# bbhTiny84.net
KiCad netlist of a schematic drawn in EAGLE
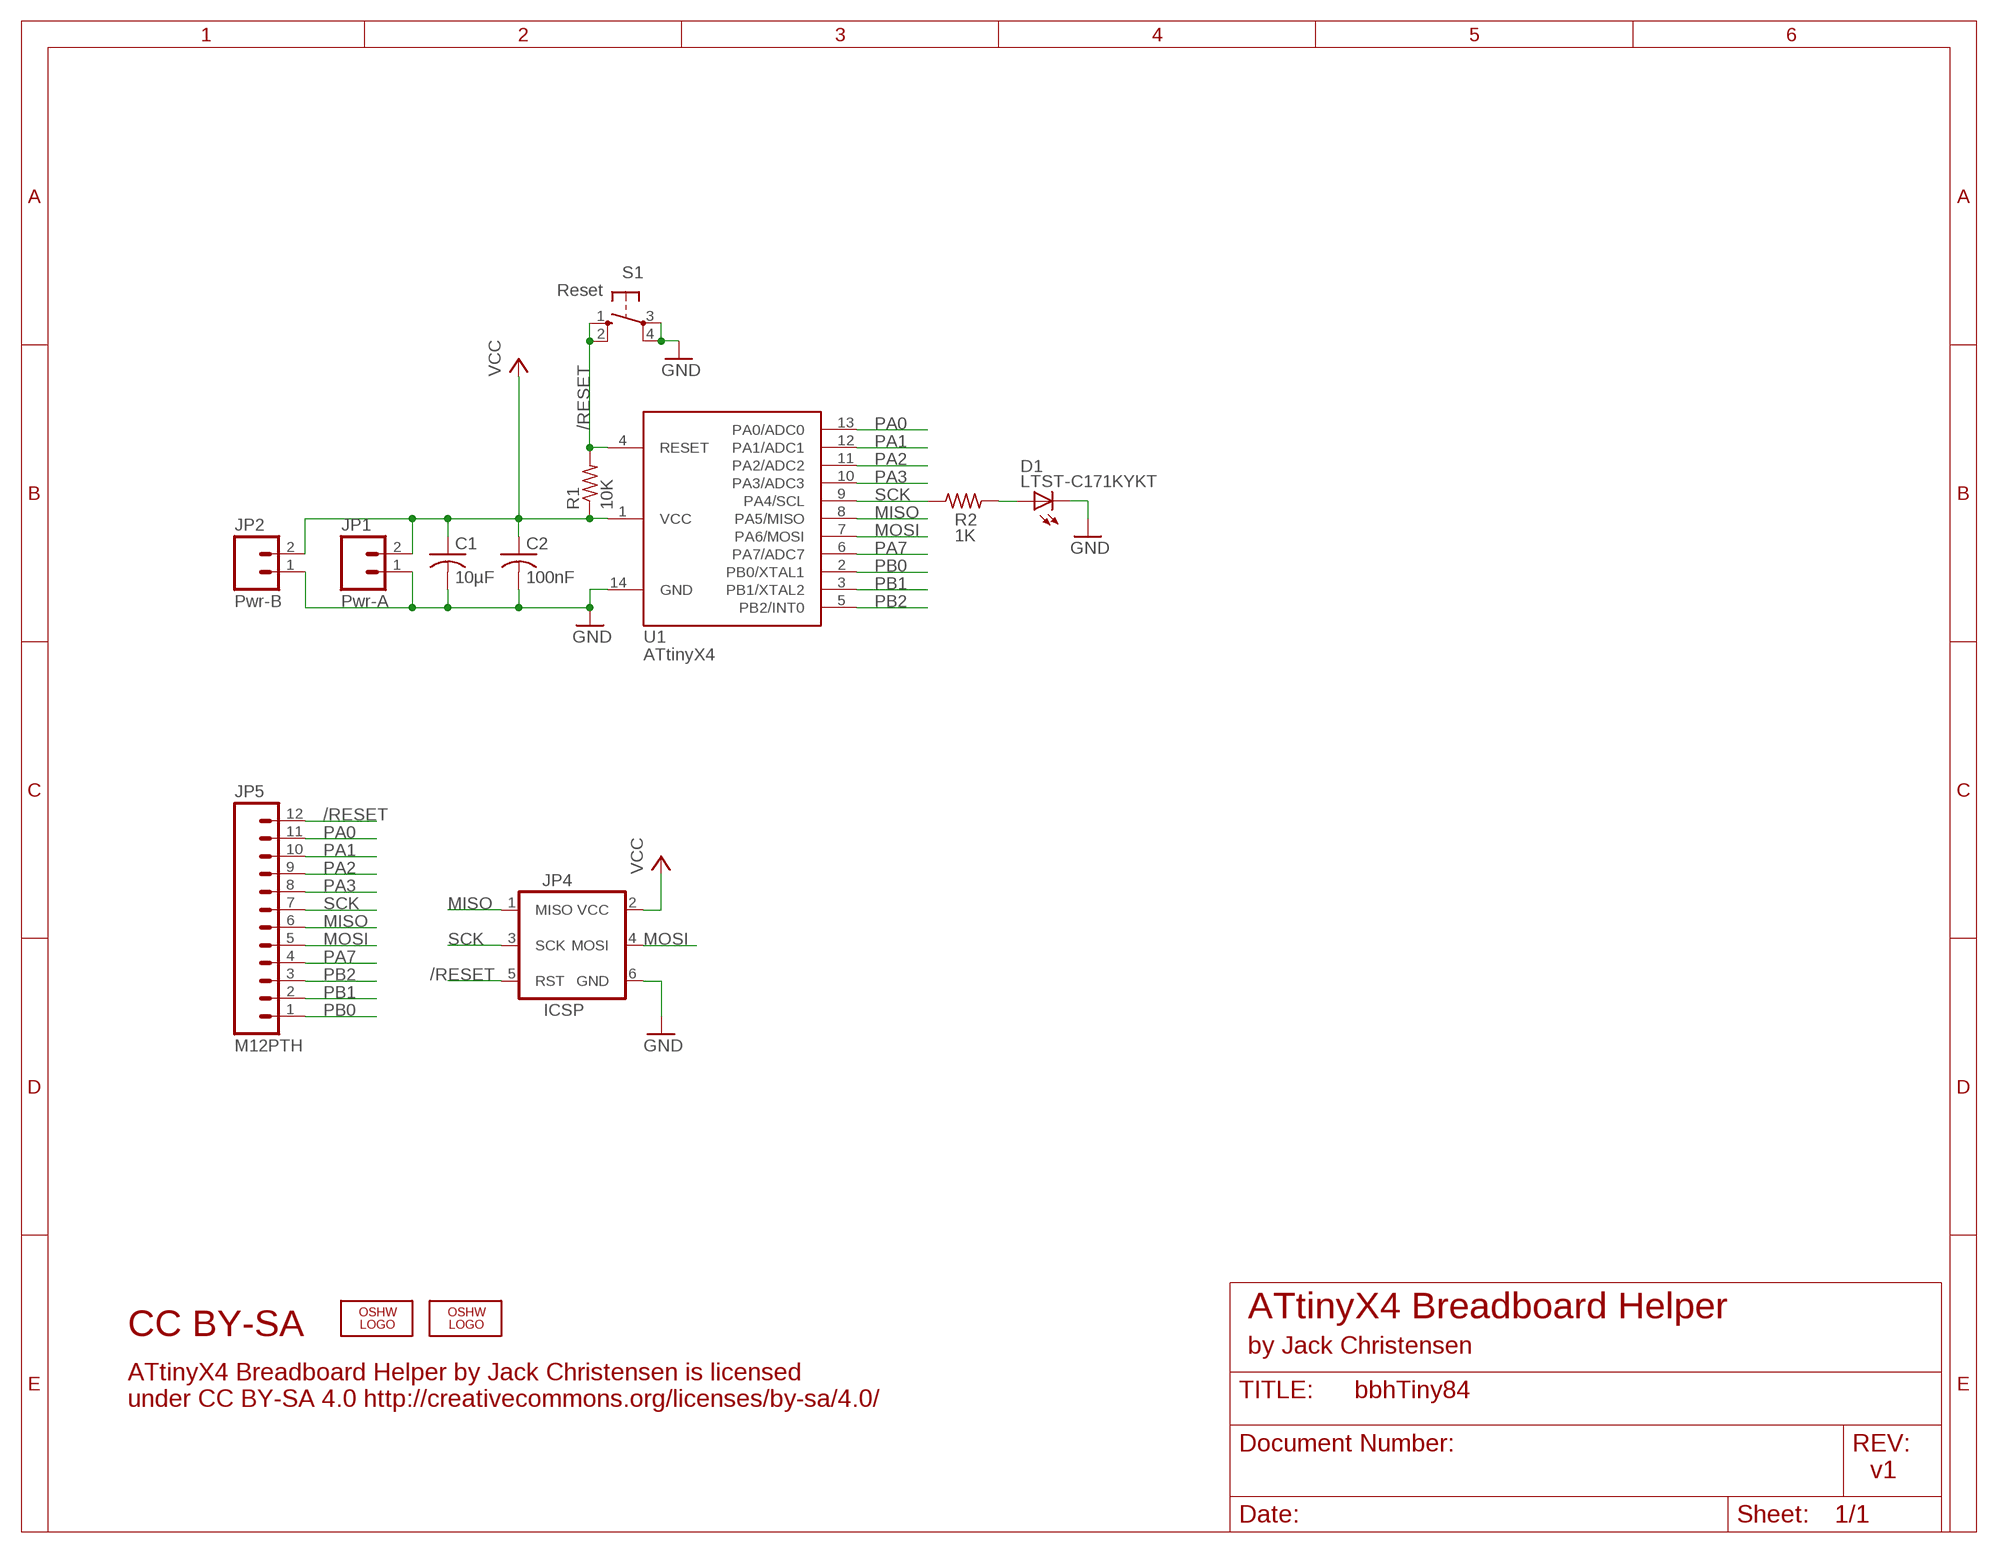
[diagram p0: schematic, sheet 1]

(export (version "E")
  (design (tool "Eeschema 10.0.6"))
  (components
    (comp (ref "C1")
      (value "10µF")
      (footprint "eagle-import:M0805")
      (libsource (lib "eagle-import") (part "C-USM0805"))
    )
    (comp (ref "C2")
      (value "100nF")
      (footprint "eagle-import:M0805")
      (libsource (lib "eagle-import") (part "C-USM0805"))
    )
    (comp (ref "D1")
      (value "LTST-C171KYKT")
      (footprint "eagle-import:D0805")
      (libsource (lib "eagle-import") (part "LEDD0805"))
    )
    (comp (ref "JP1")
      (value "Pwr-A")
      (footprint "eagle-import:1X02")
      (libsource (lib "eagle-import") (part "M02PTH"))
    )
    (comp (ref "JP2")
      (value "Pwr-B")
      (footprint "eagle-import:1X02")
      (libsource (lib "eagle-import") (part "M02PTH"))
    )
    (comp (ref "JP4")
      (value "ICSP")
      (footprint "eagle-import:2X3_LOCK")
      (libsource (lib "eagle-import") (part "AVR_SPI_PRG_62X3_LOCK"))
    )
    (comp (ref "JP5")
      (value "M12PTH")
      (footprint "eagle-import:1X12")
      (libsource (lib "eagle-import") (part "M12PTH"))
    )
    (comp (ref "LOGO1")
      (value "OSHW_LOGO_8MILX0100-NT")
      (footprint "eagle-import:OSHW_8X100_NOTEXT")
      (libsource (lib "eagle-import") (part "OSHW_LOGO_8MILX0100-NT"))
    )
    (comp (ref "LOGO2")
      (value "OSHW_LOGO_8MILX0100-NT")
      (footprint "eagle-import:OSHW_8X100_NOTEXT")
      (libsource (lib "eagle-import") (part "OSHW_LOGO_8MILX0100-NT"))
    )
    (comp (ref "R1")
      (value "10K")
      (footprint "eagle-import:M0805")
      (libsource (lib "eagle-import") (part "R-US_M0805"))
    )
    (comp (ref "R2")
      (value "1K")
      (footprint "eagle-import:M0805")
      (libsource (lib "eagle-import") (part "R-US_M0805"))
    )
    (comp (ref "S1")
      (value "Reset")
      (footprint "eagle-import:B3F-10XXOCT")
      (libsource (lib "eagle-import") (part "10-XXOCT"))
    )
    (comp (ref "U1")
      (value "ATtinyX4")
      (footprint "eagle-import:DIL14")
      (libsource (lib "eagle-import") (part "ATTINYX4DIL14"))
    )
  )
  (nets
    (net (code "1") (name "/MISO") (class "Default")
      (node (ref "JP4") (pin "1") (pinfunction "MISO_1") (pintype "passive"))
      (node (ref "JP5") (pin "6") (pinfunction "6_6") (pintype "passive"))
      (node (ref "U1") (pin "8") (pinfunction "PA5/MISO_8") (pintype "bidirectional"))
    )
    (net (code "2") (name "/MOSI") (class "Default")
      (node (ref "JP4") (pin "4") (pinfunction "MOSI_4") (pintype "passive"))
      (node (ref "JP5") (pin "5") (pinfunction "5_5") (pintype "passive"))
      (node (ref "U1") (pin "7") (pinfunction "PA6/MOSI_7") (pintype "bidirectional"))
    )
    (net (code "3") (name "/PA0") (class "Default")
      (node (ref "JP5") (pin "11") (pinfunction "11_11") (pintype "passive"))
      (node (ref "U1") (pin "13") (pinfunction "PA0/ADC0_13") (pintype "bidirectional"))
    )
    (net (code "4") (name "/PA1") (class "Default")
      (node (ref "JP5") (pin "10") (pinfunction "10_10") (pintype "passive"))
      (node (ref "U1") (pin "12") (pinfunction "PA1/ADC1_12") (pintype "bidirectional"))
    )
    (net (code "5") (name "/PA2") (class "Default")
      (node (ref "JP5") (pin "9") (pinfunction "9_9") (pintype "passive"))
      (node (ref "U1") (pin "11") (pinfunction "PA2/ADC2_11") (pintype "bidirectional"))
    )
    (net (code "6") (name "/PA3") (class "Default")
      (node (ref "JP5") (pin "8") (pinfunction "8_8") (pintype "passive"))
      (node (ref "U1") (pin "10") (pinfunction "PA3/ADC3_10") (pintype "bidirectional"))
    )
    (net (code "7") (name "/PA7") (class "Default")
      (node (ref "JP5") (pin "4") (pinfunction "4_4") (pintype "passive"))
      (node (ref "U1") (pin "6") (pinfunction "PA7/ADC7_6") (pintype "bidirectional"))
    )
    (net (code "8") (name "/PB0") (class "Default")
      (node (ref "JP5") (pin "1") (pinfunction "1_1") (pintype "passive"))
      (node (ref "U1") (pin "2") (pinfunction "PB0/XTAL1_2") (pintype "bidirectional"))
    )
    (net (code "9") (name "/PB1") (class "Default")
      (node (ref "JP5") (pin "2") (pinfunction "2_2") (pintype "passive"))
      (node (ref "U1") (pin "3") (pinfunction "PB1/XTAL2_3") (pintype "bidirectional"))
    )
    (net (code "10") (name "/PB2") (class "Default")
      (node (ref "JP5") (pin "3") (pinfunction "3_3") (pintype "passive"))
      (node (ref "U1") (pin "5") (pinfunction "PB2/INT0_5") (pintype "bidirectional"))
    )
    (net (code "11") (name "/SCK") (class "Default")
      (node (ref "JP4") (pin "3") (pinfunction "SCK_3") (pintype "passive"))
      (node (ref "JP5") (pin "7") (pinfunction "7_7") (pintype "passive"))
      (node (ref "R2") (pin "1") (pinfunction "1_1") (pintype "passive"))
      (node (ref "U1") (pin "9") (pinfunction "PA4/SCL_9") (pintype "bidirectional"))
    )
    (net (code "12") (name "/{slash}RESET") (class "Default")
      (node (ref "JP4") (pin "5") (pinfunction "RST_5") (pintype "passive"))
      (node (ref "JP5") (pin "12") (pinfunction "12_12") (pintype "passive"))
      (node (ref "R1") (pin "2") (pinfunction "2_2") (pintype "passive"))
      (node (ref "S1") (pin "1") (pinfunction "S_1") (pintype "passive"))
      (node (ref "S1") (pin "2") (pinfunction "S1_2") (pintype "passive"))
      (node (ref "U1") (pin "4") (pinfunction "RESET_4") (pintype "bidirectional"))
    )
    (net (code "13") (name "GND") (class "Default")
      (node (ref "C1") (pin "2") (pinfunction "2_2") (pintype "passive"))
      (node (ref "C2") (pin "2") (pinfunction "2_2") (pintype "passive"))
      (node (ref "D1") (pin "K") (pinfunction "C_K") (pintype "passive"))
      (node (ref "JP1") (pin "1") (pinfunction "1_1") (pintype "passive"))
      (node (ref "JP2") (pin "1") (pinfunction "1_1") (pintype "passive"))
      (node (ref "JP4") (pin "6") (pinfunction "GND_6") (pintype "passive"))
      (node (ref "S1") (pin "3") (pinfunction "P_3") (pintype "passive"))
      (node (ref "S1") (pin "4") (pinfunction "P1_4") (pintype "passive"))
      (node (ref "U1") (pin "14") (pinfunction "GND_14") (pintype "bidirectional"))
    )
    (net (code "14") (name "Net-(D1-PadA)") (class "Default")
      (node (ref "D1") (pin "A") (pinfunction "A_A") (pintype "passive"))
      (node (ref "R2") (pin "2") (pinfunction "2_2") (pintype "passive"))
    )
    (net (code "15") (name "VCC") (class "Default")
      (node (ref "C1") (pin "1") (pinfunction "1_1") (pintype "passive"))
      (node (ref "C2") (pin "1") (pinfunction "1_1") (pintype "passive"))
      (node (ref "JP1") (pin "2") (pinfunction "2_2") (pintype "passive"))
      (node (ref "JP2") (pin "2") (pinfunction "2_2") (pintype "passive"))
      (node (ref "JP4") (pin "2") (pinfunction "VCC_2") (pintype "passive"))
      (node (ref "R1") (pin "1") (pinfunction "1_1") (pintype "passive"))
      (node (ref "U1") (pin "1") (pinfunction "VCC_1") (pintype "bidirectional"))
    )
  )
)
